# Cortex_Power.net
KiCad netlist of a schematic drawn in Altium Designer
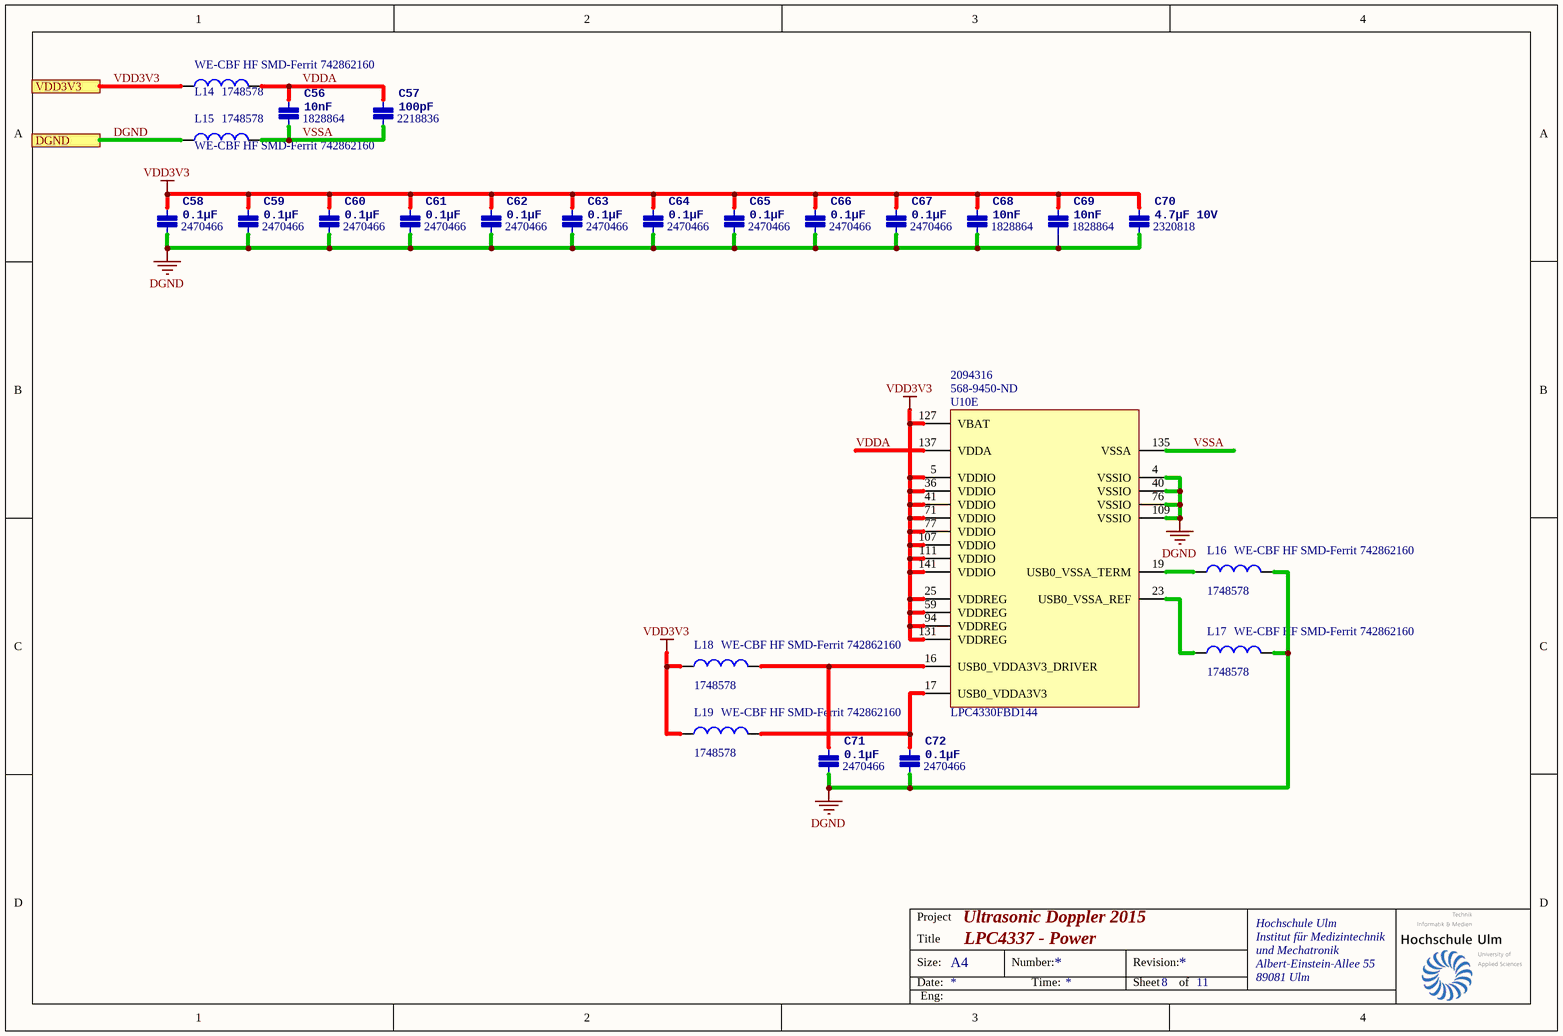
[diagram p0: Cortex_Power.SchDoc]

(export (version "E")
  (design (tool "Eeschema 10.0.6"))
  (components
    (comp (ref "C56")
      (value "10nF")
      (footprint "0402[1005]")
      (description "Cap")
      (fields (field (name "SUPPLIER PART NUMBER 1") "1828864"))
      (libsource (lib "Components") (part "Capacitor"))
    )
    (comp (ref "C57")
      (value "100pF")
      (footprint "0402[1005]")
      (description "Cap")
      (fields (field (name "SUPPLIER PART NUMBER 1") "2218836"))
      (libsource (lib "Components") (part "Capacitor"))
    )
    (comp (ref "C58")
      (value "0.1µF")
      (footprint "0402[1005]")
      (description "Cap")
      (fields (field (name "SUPPLIER PART NUMBER 1") "2470466"))
      (libsource (lib "Components") (part "Capacitor"))
    )
    (comp (ref "C59")
      (value "0.1µF")
      (footprint "0402[1005]")
      (description "Cap")
      (fields (field (name "SUPPLIER PART NUMBER 1") "2470466"))
      (libsource (lib "Components") (part "Capacitor"))
    )
    (comp (ref "C60")
      (value "0.1µF")
      (footprint "0402[1005]")
      (description "Cap")
      (fields (field (name "SUPPLIER PART NUMBER 1") "2470466"))
      (libsource (lib "Components") (part "Capacitor"))
    )
    (comp (ref "C61")
      (value "0.1µF")
      (footprint "0402[1005]")
      (description "Cap")
      (fields (field (name "SUPPLIER PART NUMBER 1") "2470466"))
      (libsource (lib "Components") (part "Capacitor"))
    )
    (comp (ref "C62")
      (value "0.1µF")
      (footprint "0402[1005]")
      (description "Cap")
      (fields (field (name "SUPPLIER PART NUMBER 1") "2470466"))
      (libsource (lib "Components") (part "Capacitor"))
    )
    (comp (ref "C63")
      (value "0.1µF")
      (footprint "0402[1005]")
      (description "Cap")
      (fields (field (name "SUPPLIER PART NUMBER 1") "2470466"))
      (libsource (lib "Components") (part "Capacitor"))
    )
    (comp (ref "C64")
      (value "0.1µF")
      (footprint "0402[1005]")
      (description "Cap")
      (fields (field (name "SUPPLIER PART NUMBER 1") "2470466"))
      (libsource (lib "Components") (part "Capacitor"))
    )
    (comp (ref "C65")
      (value "0.1µF")
      (footprint "0402[1005]")
      (description "Cap")
      (fields (field (name "SUPPLIER PART NUMBER 1") "2470466"))
      (libsource (lib "Components") (part "Capacitor"))
    )
    (comp (ref "C66")
      (value "0.1µF")
      (footprint "0402[1005]")
      (description "Cap")
      (fields (field (name "SUPPLIER PART NUMBER 1") "2470466"))
      (libsource (lib "Components") (part "Capacitor"))
    )
    (comp (ref "C67")
      (value "0.1µF")
      (footprint "0402[1005]")
      (description "Cap")
      (fields (field (name "SUPPLIER PART NUMBER 1") "2470466"))
      (libsource (lib "Components") (part "Capacitor"))
    )
    (comp (ref "C68")
      (value "10nF")
      (footprint "0402[1005]")
      (description "Cap")
      (fields (field (name "SUPPLIER PART NUMBER 1") "1828864"))
      (libsource (lib "Components") (part "Capacitor"))
    )
    (comp (ref "C69")
      (value "10nF")
      (footprint "0402[1005]")
      (description "Cap")
      (fields (field (name "SUPPLIER PART NUMBER 1") "1828864"))
      (libsource (lib "Components") (part "Capacitor"))
    )
    (comp (ref "C70")
      (value "4.7µF 10V")
      (footprint "0603[1508]")
      (description "Cap")
      (fields (field (name "SUPPLIER PART NUMBER 1") "2320818"))
      (libsource (lib "Components") (part "Capacitor"))
    )
    (comp (ref "C71")
      (value "0.1µF")
      (footprint "0402[1005]")
      (description "Cap")
      (fields (field (name "SUPPLIER PART NUMBER 1") "2470466"))
      (libsource (lib "Components") (part "Capacitor"))
    )
    (comp (ref "C72")
      (value "0.1µF")
      (footprint "0402[1005]")
      (description "Cap")
      (fields (field (name "SUPPLIER PART NUMBER 1") "2470466"))
      (libsource (lib "Components") (part "Capacitor"))
    )
    (comp (ref "L14")
      (value "WE-CBF HF SMD-Ferrit 742862160")
      (footprint "0603[1508]")
      (description "Ferrit")
      (fields (field (name "SUPPLIER PART NUMBER 1") "1748578") (field (name "PUBLISHER") "Altium Limited"))
      (libsource (lib "Components") (part "Inductor"))
    )
    (comp (ref "L15")
      (value "WE-CBF HF SMD-Ferrit 742862160")
      (footprint "0603[1508]")
      (description "Ferrit")
      (fields (field (name "SUPPLIER PART NUMBER 1") "1748578") (field (name "PUBLISHER") "Altium Limited"))
      (libsource (lib "Components") (part "Inductor"))
    )
    (comp (ref "L16")
      (value "WE-CBF HF SMD-Ferrit 742862160")
      (footprint "0603[1508]")
      (description "Ferrit")
      (fields (field (name "SUPPLIER PART NUMBER 1") "1748578") (field (name "PUBLISHER") "Altium Limited"))
      (libsource (lib "Components") (part "Inductor"))
    )
    (comp (ref "L17")
      (value "WE-CBF HF SMD-Ferrit 742862160")
      (footprint "0603[1508]")
      (description "Ferrit")
      (fields (field (name "SUPPLIER PART NUMBER 1") "1748578") (field (name "PUBLISHER") "Altium Limited"))
      (libsource (lib "Components") (part "Inductor"))
    )
    (comp (ref "L18")
      (value "WE-CBF HF SMD-Ferrit 742862160")
      (footprint "0603[1508]")
      (description "Ferrit")
      (fields (field (name "SUPPLIER PART NUMBER 1") "1748578") (field (name "PUBLISHER") "Altium Limited"))
      (libsource (lib "Components") (part "Inductor"))
    )
    (comp (ref "L19")
      (value "WE-CBF HF SMD-Ferrit 742862160")
      (footprint "0603[1508]")
      (description "Ferrit")
      (fields (field (name "SUPPLIER PART NUMBER 1") "1748578") (field (name "PUBLISHER") "Altium Limited"))
      (libsource (lib "Components") (part "Inductor"))
    )
    (comp (ref "U10")
      (value "LPC4330FBD144")
      (footprint "LQFP144")
      (fields
        (field (name "SUPPLIER PART NUMBER 1") "568-9450-ND")
        (field (name "SUPPLIER PART NUMBER 2") "2094316")
      )
      (libsource (lib "USD Parts") (part "LPC4330FBD144"))
    )
  )
  (nets
    (net (code "1") (name "/VDDA") (class "Default")
      (node (ref "C56") (pin "1") (pinfunction "P$1_1") (pintype "passive"))
      (node (ref "C57") (pin "1") (pinfunction "P$1_1") (pintype "passive"))
      (node (ref "L14") (pin "2") (pinfunction "2_2") (pintype "passive"))
      (node (ref "U10") (pin "137") (pinfunction "VDDA_137") (pintype "power_in"))
    )
    (net (code "2") (name "/VSSA") (class "Default")
      (node (ref "C56") (pin "2") (pinfunction "P$2_2") (pintype "passive"))
      (node (ref "C57") (pin "2") (pinfunction "P$2_2") (pintype "passive"))
      (node (ref "L15") (pin "2") (pinfunction "2_2") (pintype "passive"))
      (node (ref "U10") (pin "135") (pinfunction "VSSA_135") (pintype "power_in"))
    )
    (net (code "3") (name "DGND") (class "Default")
      (node (ref "C58") (pin "2") (pinfunction "P$2_2") (pintype "passive"))
      (node (ref "C59") (pin "2") (pinfunction "P$2_2") (pintype "passive"))
      (node (ref "C60") (pin "2") (pinfunction "P$2_2") (pintype "passive"))
      (node (ref "C61") (pin "2") (pinfunction "P$2_2") (pintype "passive"))
      (node (ref "C62") (pin "2") (pinfunction "P$2_2") (pintype "passive"))
      (node (ref "C63") (pin "2") (pinfunction "P$2_2") (pintype "passive"))
      (node (ref "C64") (pin "2") (pinfunction "P$2_2") (pintype "passive"))
      (node (ref "C65") (pin "2") (pinfunction "P$2_2") (pintype "passive"))
      (node (ref "C66") (pin "2") (pinfunction "P$2_2") (pintype "passive"))
      (node (ref "C67") (pin "2") (pinfunction "P$2_2") (pintype "passive"))
      (node (ref "C68") (pin "2") (pinfunction "P$2_2") (pintype "passive"))
      (node (ref "C69") (pin "2") (pinfunction "P$2_2") (pintype "passive"))
      (node (ref "C70") (pin "2") (pinfunction "P$2_2") (pintype "passive"))
      (node (ref "C71") (pin "2") (pinfunction "P$2_2") (pintype "passive"))
      (node (ref "C72") (pin "2") (pinfunction "P$2_2") (pintype "passive"))
      (node (ref "L15") (pin "1") (pinfunction "1_1") (pintype "passive"))
      (node (ref "L16") (pin "2") (pinfunction "2_2") (pintype "passive"))
      (node (ref "L17") (pin "2") (pinfunction "2_2") (pintype "passive"))
      (node (ref "U10") (pin "109") (pinfunction "VSSIO_109") (pintype "power_in"))
      (node (ref "U10") (pin "4") (pinfunction "VSSIO_4") (pintype "power_in"))
      (node (ref "U10") (pin "40") (pinfunction "VSSIO_40") (pintype "power_in"))
      (node (ref "U10") (pin "76") (pinfunction "VSSIO_76") (pintype "power_in"))
    )
    (net (code "4") (name "Net-(C71-P$1)") (class "Default")
      (node (ref "C71") (pin "1") (pinfunction "P$1_1") (pintype "passive"))
      (node (ref "L18") (pin "2") (pinfunction "2_2") (pintype "passive"))
      (node (ref "U10") (pin "16") (pinfunction "USB0_VDDA3V3_DRIVER_16") (pintype "power_in"))
    )
    (net (code "5") (name "Net-(C72-P$1)") (class "Default")
      (node (ref "C72") (pin "1") (pinfunction "P$1_1") (pintype "passive"))
      (node (ref "L19") (pin "2") (pinfunction "2_2") (pintype "passive"))
      (node (ref "U10") (pin "17") (pinfunction "USB0_VDDA3V3_17") (pintype "power_in"))
    )
    (net (code "6") (name "Net-(U10E-USB0_VSSA_REF)") (class "Default")
      (node (ref "L17") (pin "1") (pinfunction "1_1") (pintype "passive"))
      (node (ref "U10") (pin "23") (pinfunction "USB0_VSSA_REF_23") (pintype "power_in"))
    )
    (net (code "7") (name "Net-(U10E-USB0_VSSA_TERM)") (class "Default")
      (node (ref "L16") (pin "1") (pinfunction "1_1") (pintype "passive"))
      (node (ref "U10") (pin "19") (pinfunction "USB0_VSSA_TERM_19") (pintype "power_in"))
    )
    (net (code "8") (name "VDD3V3") (class "Default")
      (node (ref "C58") (pin "1") (pinfunction "P$1_1") (pintype "passive"))
      (node (ref "C59") (pin "1") (pinfunction "P$1_1") (pintype "passive"))
      (node (ref "C60") (pin "1") (pinfunction "P$1_1") (pintype "passive"))
      (node (ref "C61") (pin "1") (pinfunction "P$1_1") (pintype "passive"))
      (node (ref "C62") (pin "1") (pinfunction "P$1_1") (pintype "passive"))
      (node (ref "C63") (pin "1") (pinfunction "P$1_1") (pintype "passive"))
      (node (ref "C64") (pin "1") (pinfunction "P$1_1") (pintype "passive"))
      (node (ref "C65") (pin "1") (pinfunction "P$1_1") (pintype "passive"))
      (node (ref "C66") (pin "1") (pinfunction "P$1_1") (pintype "passive"))
      (node (ref "C67") (pin "1") (pinfunction "P$1_1") (pintype "passive"))
      (node (ref "C68") (pin "1") (pinfunction "P$1_1") (pintype "passive"))
      (node (ref "C69") (pin "1") (pinfunction "P$1_1") (pintype "passive"))
      (node (ref "C70") (pin "1") (pinfunction "P$1_1") (pintype "passive"))
      (node (ref "L14") (pin "1") (pinfunction "1_1") (pintype "passive"))
      (node (ref "L18") (pin "1") (pinfunction "1_1") (pintype "passive"))
      (node (ref "L19") (pin "1") (pinfunction "1_1") (pintype "passive"))
      (node (ref "U10") (pin "107") (pinfunction "VDDIO_107") (pintype "power_in"))
      (node (ref "U10") (pin "111") (pinfunction "VDDIO_111") (pintype "power_in"))
      (node (ref "U10") (pin "127") (pinfunction "VBAT_127") (pintype "power_in"))
      (node (ref "U10") (pin "131") (pinfunction "VDDREG_131") (pintype "power_in"))
      (node (ref "U10") (pin "141") (pinfunction "VDDIO_141") (pintype "power_in"))
      (node (ref "U10") (pin "25") (pinfunction "VDDREG_25") (pintype "power_in"))
      (node (ref "U10") (pin "36") (pinfunction "VDDIO_36") (pintype "power_in"))
      (node (ref "U10") (pin "41") (pinfunction "VDDIO_41") (pintype "power_in"))
      (node (ref "U10") (pin "5") (pinfunction "VDDIO_5") (pintype "power_in"))
      (node (ref "U10") (pin "59") (pinfunction "VDDREG_59") (pintype "power_in"))
      (node (ref "U10") (pin "71") (pinfunction "VDDIO_71") (pintype "power_in"))
      (node (ref "U10") (pin "77") (pinfunction "VDDIO_77") (pintype "power_in"))
      (node (ref "U10") (pin "94") (pinfunction "VDDREG_94") (pintype "power_in"))
    )
  )
)
